# H01R0_Backend.net
KiCad netlist of a schematic drawn in Altium Designer
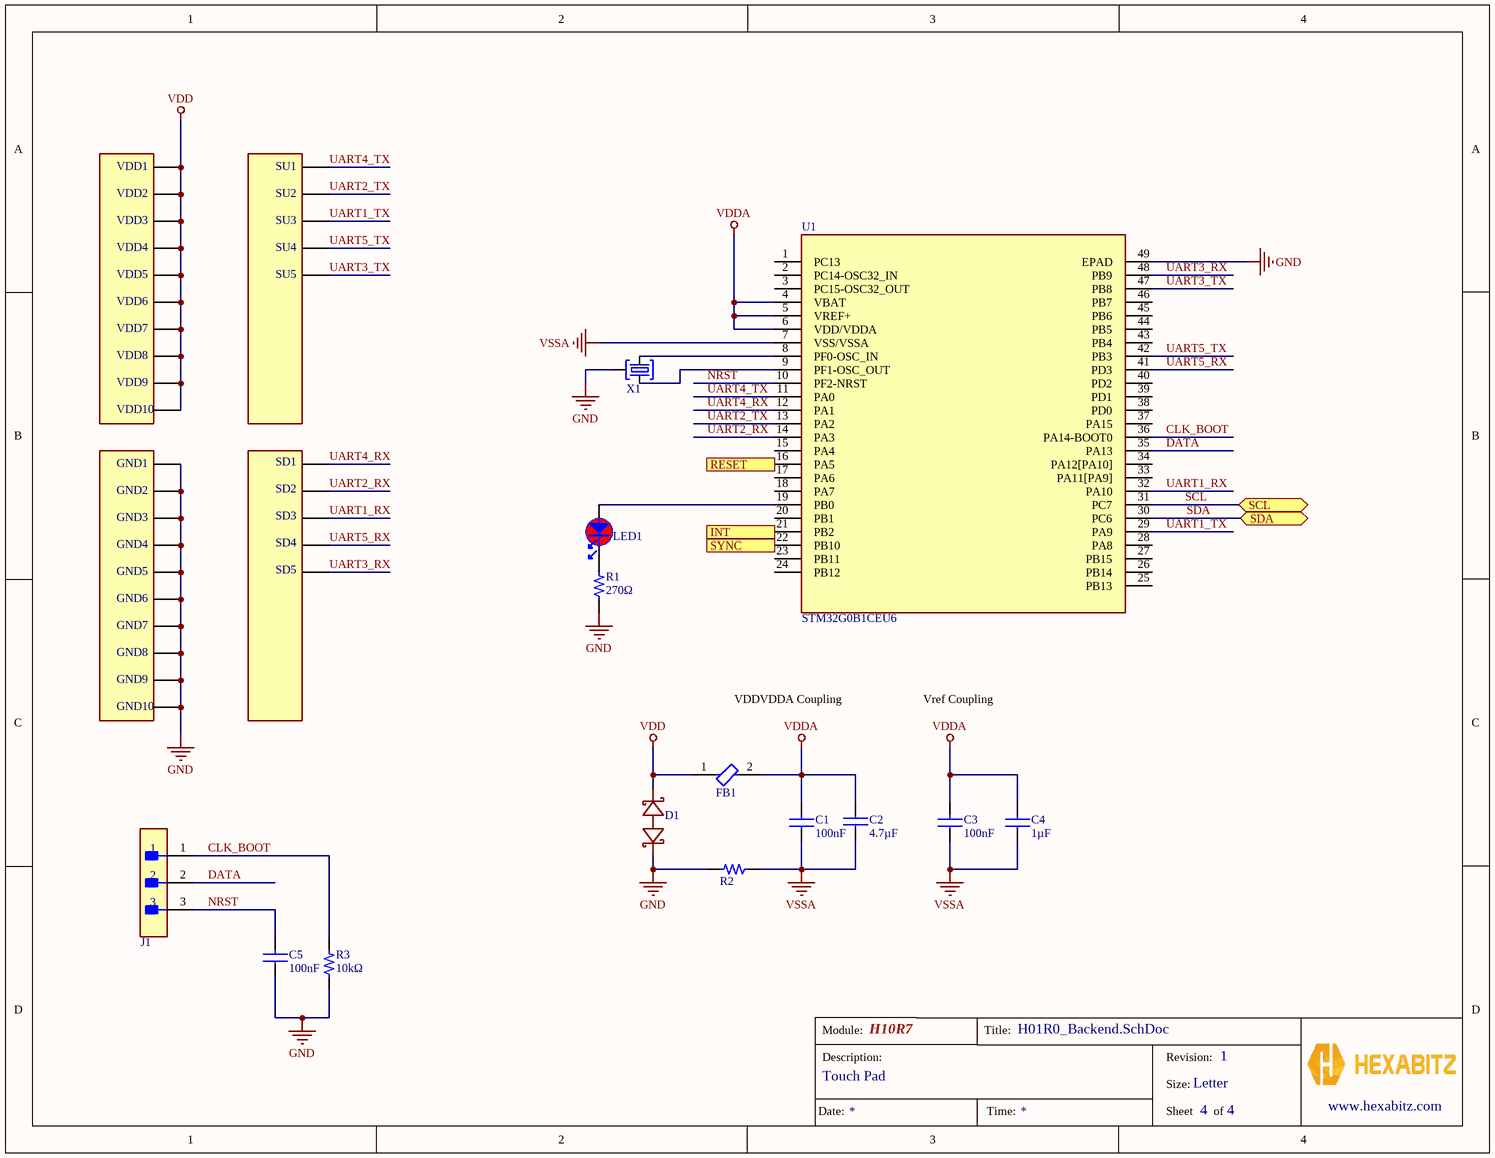
[diagram p0: H01R0_Backend.SchDoc]

(export (version "E")
  (design (tool "Eeschema 10.0.6"))
  (components
    (comp (ref "C1")
      (value "100nF")
      (footprint "C0603")
      (fields
        (field (name "MANUFACTURER") "Samsung Electro-Mechanics")
        (field (name "MANUFACTURER PART NUMBER") "CL10B104KA8NNNC")
        (field (name "TOLERANCE") "10%")
      )
      (libsource (lib "Hexabitz Altium Library") (part "generic Capacitor"))
    )
    (comp (ref "C2")
      (value "4.7µF")
      (footprint "C0805")
      (fields
        (field (name "MANUFACTURER") "Samsung Electro-Mechanics")
        (field (name "MANUFACTURER PART NUMBER") "CL21X475KAQNNNE")
        (field (name "TOLERANCE") "10%")
      )
      (libsource (lib "Hexabitz Altium Library") (part "generic Capacitor"))
    )
    (comp (ref "C3")
      (value "100nF")
      (footprint "C0603")
      (fields
        (field (name "MANUFACTURER") "Samsung Electro-Mechanics")
        (field (name "MANUFACTURER PART NUMBER") "CL10B104KA8NNNC")
        (field (name "TOLERANCE") "10%")
      )
      (libsource (lib "Hexabitz Altium Library") (part "generic Capacitor"))
    )
    (comp (ref "C4")
      (value "1µF")
      (footprint "C0805")
      (description "Ceramic Capacitor, Ceramic, 16V, 10% +Tol, 10% -Tol, X7R, 15% TC, 1uF, Surface Mount, 0805")
      (fields
        (field (name "MANUFACTURER") "Yageo Group")
        (field (name "MANUFACTURER PART NUMBER") "CC0805KKX7R7BB105")
      )
      (libsource (lib "Hexabitz Altium Library") (part "generic Capacitor"))
    )
    (comp (ref "C5")
      (value "100nF")
      (footprint "C0603")
      (fields
        (field (name "MANUFACTURER") "Samsung Electro-Mechanics")
        (field (name "MANUFACTURER PART NUMBER") "CL10B104KA8NNNC")
        (field (name "TOLERANCE") "10%")
      )
      (libsource (lib "Hexabitz Altium Library") (part "generic Capacitor"))
    )
    (comp (ref "D1")
      (value "CDSOD323-T03SC")
      (footprint "SOD2513X114N")
      (description "A 3V, 350W, bi-directional, standard capacitance, SOD323 pkg TVS Diode ¦ Bourns CDSOD323-T03SC")
      (fields (field (name "MANUFACTURER") "Bourns"))
      (libsource (lib "Hexabitz Altium Library") (part "CDSOD323-T03SC"))
    )
    (comp (ref "FB1")
      (value "MMZ1608Y300B")
      (footprint "FP-MMZ1608-0_8-MFG")
      (description "Ferrite Beads 0603 30ohms 1500mA Signal Line AEC-Q200")
      (fields
        (field (name "MANUFACTURER") "TDK")
        (field (name "MANUFACTURER PART NUMBER") "MMZ1608Y300BTD25")
      )
      (libsource (lib "Hexabitz Altium Library") (part "MMZ1608Y300B"))
    )
    (comp (ref "GND1")
      (value "HEXABIT_UART_PORT")
      (footprint "HEXABIT_POWER_PORT_D")
      (libsource (lib "hexabitz_connectors.Library") (part "HEXABIT_POWER_PORT_D"))
    )
    (comp (ref "GND2")
      (value "HEXABIT_UART_PORT")
      (footprint "HEXABIT_POWER_PORT_D")
      (libsource (lib "hexabitz_connectors.Library") (part "HEXABIT_POWER_PORT_D"))
    )
    (comp (ref "GND3")
      (value "HEXABIT_UART_PORT")
      (footprint "HEXABIT_POWER_PORT_D_300R")
      (libsource (lib "hexabitz_connectors.Library") (part "HEXABIT_POWER_PORT_D_300R"))
    )
    (comp (ref "GND4")
      (value "HEXABIT_UART_PORT")
      (footprint "HEXABIT_POWER_PORT_D")
      (libsource (lib "hexabitz_connectors.Library") (part "HEXABIT_POWER_PORT_D"))
    )
    (comp (ref "GND5")
      (value "HEXABIT_UART_PORT")
      (footprint "HEXABIT_POWER_PORT_D")
      (libsource (lib "hexabitz_connectors.Library") (part "HEXABIT_POWER_PORT_D"))
    )
    (comp (ref "GND6")
      (value "HEXABIT_UART_PORT")
      (footprint "HEXABIT_POWER_PORT_D")
      (libsource (lib "hexabitz_connectors.Library") (part "HEXABIT_POWER_PORT_D"))
    )
    (comp (ref "GND7")
      (value "HEXABIT_UART_PORT")
      (footprint "HEXABIT_POWER_PORT_D")
      (libsource (lib "hexabitz_connectors.Library") (part "HEXABIT_POWER_PORT_D"))
    )
    (comp (ref "GND8")
      (value "HEXABIT_UART_PORT")
      (footprint "HEXABIT_POWER_PORT_D_300L")
      (libsource (lib "hexabitz_connectors.Library") (part "HEXABIT_POWER_PORT_D_300L"))
    )
    (comp (ref "GND9")
      (value "HEXABIT_UART_PORT")
      (footprint "HEXABIT_POWER_PORT_D")
      (libsource (lib "hexabitz_connectors.Library") (part "HEXABIT_POWER_PORT_D"))
    )
    (comp (ref "GND10")
      (value "HEXABIT_UART_PORT")
      (footprint "HEXABIT_POWER_PORT_D")
      (libsource (lib "hexabitz_connectors.Library") (part "HEXABIT_POWER_PORT_D"))
    )
    (comp (ref "J1")
      (value "TSW-103-14-G-S")
      (footprint "FP-TSW-103-14-G-S-MFG")
      (description "CONN HEADER VERT 3POS 2.54MM")
      (libsource (lib "Altium Content Vault") (part "cd3439d6ef35ae5d9b27ec4fdd3e828"))
    )
    (comp (ref "LED1")
      (value "VLMS1300-GS08")
      (footprint "FP-6_541-5092_01-4-MFG")
      (description "LED Uni-Color Super Red 639nm 2-Pin Chip 0603(1608Metric) T/R")
      (fields (field (name "MANUFACTURER") "Vishay Semiconductors"))
      (libsource (lib "Hexabitz Altium Library") (part "VLMS1300-GS08"))
    )
    (comp (ref "R1")
      (value "270Ω")
      (footprint "R0603")
      (description "Res Thick Film 0603 270 Ohm 5% 0.1W(1/10W) ±200ppm/C Pad SMD Automotive T/R")
      (fields
        (field (name "MANUFACTURER") "Panasonic")
        (field (name "MANUFACTURER PART NUMBER") "ERJ-3GEYJ271V")
      )
      (libsource (lib "") (part "generic Resistor_1"))
    )
    (comp (ref "R2")
      (value "Manufacturer Part Number")
      (footprint "R0603")
      (libsource (lib "Hexabitz Altium Library") (part "generic Resistor"))
    )
    (comp (ref "R3")
      (value "10kΩ")
      (footprint "R0603")
      (description "100mW Thick Film Resistors ±100ppm/℃ ±1% 10kΩ 0603 Chip Resistor - Surface Mount ROHS")
      (fields
        (field (name "MANUFACTURER") "Yageo Group")
        (field (name "MANUFACTURER PART NUMBER") "RC0603FR-0710KL")
      )
      (libsource (lib "") (part "generic Resistor_2"))
    )
    (comp (ref "SD1")
      (value "HEXABIT_UART_PORT")
      (footprint "HEXABIT_UART_PORT_D")
      (libsource (lib "hexabitz_connectors.Library") (part "HEXABIT_UART_PORT_D"))
    )
    (comp (ref "SD2")
      (value "HEXABIT_UART_PORT")
      (footprint "HEXABIT_UART_PORT_D")
      (libsource (lib "hexabitz_connectors.Library") (part "HEXABIT_UART_PORT_D"))
    )
    (comp (ref "SD3")
      (value "HEXABIT_UART_PORT")
      (footprint "HEXABIT_UART_PORT_D")
      (libsource (lib "hexabitz_connectors.Library") (part "HEXABIT_UART_PORT_D"))
    )
    (comp (ref "SD4")
      (value "HEXABIT_UART_PORT")
      (footprint "HEXABIT_UART_PORT_D")
      (libsource (lib "hexabitz_connectors.Library") (part "HEXABIT_UART_PORT_D"))
    )
    (comp (ref "SD5")
      (value "HEXABIT_UART_PORT")
      (footprint "HEXABIT_UART_PORT_D")
      (libsource (lib "hexabitz_connectors.Library") (part "HEXABIT_UART_PORT_D"))
    )
    (comp (ref "SU1")
      (value "HEXABIT_UART_PORT")
      (footprint "HEXABIT_UART_PORT_U")
      (libsource (lib "hexabitz_connectors.Library") (part "HEXABIT_UART_PORT_U"))
    )
    (comp (ref "SU2")
      (value "HEXABIT_UART_PORT")
      (footprint "HEXABIT_UART_PORT_U")
      (libsource (lib "hexabitz_connectors.Library") (part "HEXABIT_UART_PORT_U"))
    )
    (comp (ref "SU3")
      (value "HEXABIT_UART_PORT")
      (footprint "HEXABIT_UART_PORT_U")
      (libsource (lib "hexabitz_connectors.Library") (part "HEXABIT_UART_PORT_U"))
    )
    (comp (ref "SU4")
      (value "HEXABIT_UART_PORT")
      (footprint "HEXABIT_UART_PORT_U")
      (libsource (lib "hexabitz_connectors.Library") (part "HEXABIT_UART_PORT_U"))
    )
    (comp (ref "SU5")
      (value "HEXABIT_UART_PORT")
      (footprint "HEXABIT_UART_PORT_U")
      (libsource (lib "hexabitz_connectors.Library") (part "HEXABIT_UART_PORT_U"))
    )
    (comp (ref "U1")
      (value "STM32G0B1CEU6")
      (footprint "QFN50P700X700X65-49N-D")
      (description "MCU 32-bit ARM Cortex M0+ RISC 512KB Flash 1.8V/2.5V/3.3V 48-Pin UFQFPN EP Tray")
      (fields
        (field (name "MANUFACTURER") "STMicroelectronics")
        (field (name "MANUFACTURER PART NUMBER") "STM32G0B1CEU6")
      )
      (libsource (lib "Hexabitz Altium Library") (part "STM32G0B1CEU6"))
    )
    (comp (ref "VDD1")
      (value "HEXABIT_UART_PORT")
      (footprint "HEXABIT_POWER_PORT_U")
      (libsource (lib "hexabitz_connectors.Library") (part "HEXABIT_POWER_PORT_U"))
    )
    (comp (ref "VDD2")
      (value "HEXABIT_UART_PORT")
      (footprint "HEXABIT_POWER_PORT_U")
      (libsource (lib "hexabitz_connectors.Library") (part "HEXABIT_POWER_PORT_U"))
    )
    (comp (ref "VDD3")
      (value "HEXABIT_UART_PORT")
      (footprint "HEXABIT_POWER_PORT_U_300R")
      (libsource (lib "hexabitz_connectors.Library") (part "HEXABIT_POWER_PORT_U_300R"))
    )
    (comp (ref "VDD4")
      (value "HEXABIT_UART_PORT")
      (footprint "HEXABIT_POWER_PORT_U")
      (libsource (lib "hexabitz_connectors.Library") (part "HEXABIT_POWER_PORT_U"))
    )
    (comp (ref "VDD5")
      (value "HEXABIT_UART_PORT")
      (footprint "HEXABIT_POWER_PORT_U")
      (libsource (lib "hexabitz_connectors.Library") (part "HEXABIT_POWER_PORT_U"))
    )
    (comp (ref "VDD6")
      (value "HEXABIT_UART_PORT")
      (footprint "HEXABIT_POWER_PORT_U")
      (libsource (lib "hexabitz_connectors.Library") (part "HEXABIT_POWER_PORT_U"))
    )
    (comp (ref "VDD7")
      (value "HEXABIT_UART_PORT")
      (footprint "HEXABIT_POWER_PORT_U")
      (libsource (lib "hexabitz_connectors.Library") (part "HEXABIT_POWER_PORT_U"))
    )
    (comp (ref "VDD8")
      (value "HEXABIT_UART_PORT")
      (footprint "HEXABIT_POWER_PORT_U_300L")
      (libsource (lib "hexabitz_connectors.Library") (part "HEXABIT_POWER_PORT_U_300L"))
    )
    (comp (ref "VDD9")
      (value "HEXABIT_UART_PORT")
      (footprint "HEXABIT_POWER_PORT_U")
      (libsource (lib "hexabitz_connectors.Library") (part "HEXABIT_POWER_PORT_U"))
    )
    (comp (ref "VDD10")
      (value "HEXABIT_UART_PORT")
      (footprint "HEXABIT_POWER_PORT_U")
      (libsource (lib "hexabitz_connectors.Library") (part "HEXABIT_POWER_PORT_U"))
    )
    (comp (ref "X1")
      (value "CSTCE8M00G52Z-R0")
      (footprint "XTALL_CSTCE8M00G52")
      (description "Ceramic Resonator 8MHz ±0.5% (Tol) ±0.2% (Stability) 10pF 40Ohm 3-Pin CSMD T/R")
      (fields (field (name "MANUFACTURER") "Murata") (field (name "TOLERANCE") "0.5%"))
      (libsource (lib "Hexabitz Altium Library") (part "CSTCE8M00G52Z-R0"))
    )
  )
  (nets
    (net (code "1") (name "/CLK_BOOT") (class "Default")
      (node (ref "J1") (pin "1") (pinfunction "1_1") (pintype "passive"))
      (node (ref "R3") (pin "1") (pinfunction "1_1") (pintype "passive"))
      (node (ref "U1") (pin "36") (pinfunction "PA14-BOOT0_36") (pintype "passive"))
    )
    (net (code "2") (name "/DATA") (class "Default")
      (node (ref "J1") (pin "2") (pinfunction "2_2") (pintype "passive"))
      (node (ref "U1") (pin "35") (pinfunction "PA13_35") (pintype "passive"))
    )
    (net (code "3") (name "/INT") (class "Default")
      (node (ref "U1") (pin "21") (pinfunction "PB2_21") (pintype "passive"))
    )
    (net (code "4") (name "/NRST") (class "Default")
      (node (ref "C5") (pin "2") (pinfunction "2_2") (pintype "passive"))
      (node (ref "J1") (pin "3") (pinfunction "3_3") (pintype "passive"))
      (node (ref "U1") (pin "10") (pinfunction "PF2-NRST_10") (pintype "passive"))
    )
    (net (code "5") (name "/RESET") (class "Default")
      (node (ref "U1") (pin "16") (pinfunction "PA5_16") (pintype "passive"))
    )
    (net (code "6") (name "/SCL") (class "Default")
      (node (ref "U1") (pin "31") (pinfunction "PC7_31") (pintype "passive"))
    )
    (net (code "7") (name "/SDA") (class "Default")
      (node (ref "U1") (pin "30") (pinfunction "PC6_30") (pintype "passive"))
    )
    (net (code "8") (name "/SYNC") (class "Default")
      (node (ref "U1") (pin "22") (pinfunction "PB10_22") (pintype "passive"))
    )
    (net (code "9") (name "/UART1_RX") (class "Default")
      (node (ref "SD3") (pin "UART_D") (pinfunction "UART_D_UART_D") (pintype "passive"))
      (node (ref "U1") (pin "32") (pinfunction "PA10_32") (pintype "passive"))
    )
    (net (code "10") (name "/UART1_TX") (class "Default")
      (node (ref "SU3") (pin "UART_U") (pinfunction "UART_U_UART_U") (pintype "passive"))
      (node (ref "U1") (pin "29") (pinfunction "PA9_29") (pintype "passive"))
    )
    (net (code "11") (name "/UART2_RX") (class "Default")
      (node (ref "SD2") (pin "UART_D") (pinfunction "UART_D_UART_D") (pintype "passive"))
      (node (ref "U1") (pin "14") (pinfunction "PA3_14") (pintype "passive"))
    )
    (net (code "12") (name "/UART2_TX") (class "Default")
      (node (ref "SU2") (pin "UART_U") (pinfunction "UART_U_UART_U") (pintype "passive"))
      (node (ref "U1") (pin "13") (pinfunction "PA2_13") (pintype "passive"))
    )
    (net (code "13") (name "/UART3_RX") (class "Default")
      (node (ref "SD5") (pin "UART_D") (pinfunction "UART_D_UART_D") (pintype "passive"))
      (node (ref "U1") (pin "48") (pinfunction "PB9_48") (pintype "passive"))
    )
    (net (code "14") (name "/UART3_TX") (class "Default")
      (node (ref "SU5") (pin "UART_U") (pinfunction "UART_U_UART_U") (pintype "passive"))
      (node (ref "U1") (pin "47") (pinfunction "PB8_47") (pintype "passive"))
    )
    (net (code "15") (name "/UART4_RX") (class "Default")
      (node (ref "SD1") (pin "UART_D") (pinfunction "UART_D_UART_D") (pintype "passive"))
      (node (ref "U1") (pin "12") (pinfunction "PA1_12") (pintype "passive"))
    )
    (net (code "16") (name "/UART4_TX") (class "Default")
      (node (ref "SU1") (pin "UART_U") (pinfunction "UART_U_UART_U") (pintype "passive"))
      (node (ref "U1") (pin "11") (pinfunction "PA0_11") (pintype "passive"))
    )
    (net (code "17") (name "/UART5_RX") (class "Default")
      (node (ref "SD4") (pin "UART_D") (pinfunction "UART_D_UART_D") (pintype "passive"))
      (node (ref "U1") (pin "41") (pinfunction "PD3_41") (pintype "passive"))
    )
    (net (code "18") (name "/UART5_TX") (class "Default")
      (node (ref "SU4") (pin "UART_U") (pinfunction "UART_U_UART_U") (pintype "passive"))
      (node (ref "U1") (pin "42") (pinfunction "PB3_42") (pintype "passive"))
    )
    (net (code "19") (name "GND") (class "Default")
      (node (ref "C5") (pin "1") (pinfunction "1_1") (pintype "passive"))
      (node (ref "D1") (pin "1") (pinfunction "A_1") (pintype "passive"))
      (node (ref "GND1") (pin "Pwr_D") (pinfunction "Pwr_D_Pwr_D") (pintype "passive"))
      (node (ref "GND10") (pin "Pwr_D") (pinfunction "Pwr_D_Pwr_D") (pintype "passive"))
      (node (ref "GND2") (pin "Pwr_D") (pinfunction "Pwr_D_Pwr_D") (pintype "passive"))
      (node (ref "GND3") (pin "Pwr_D") (pinfunction "Pwr_D_Pwr_D") (pintype "passive"))
      (node (ref "GND4") (pin "Pwr_D") (pinfunction "Pwr_D_Pwr_D") (pintype "passive"))
      (node (ref "GND5") (pin "Pwr_D") (pinfunction "Pwr_D_Pwr_D") (pintype "passive"))
      (node (ref "GND6") (pin "Pwr_D") (pinfunction "Pwr_D_Pwr_D") (pintype "passive"))
      (node (ref "GND7") (pin "Pwr_D") (pinfunction "Pwr_D_Pwr_D") (pintype "passive"))
      (node (ref "GND8") (pin "Pwr_D") (pinfunction "Pwr_D_Pwr_D") (pintype "passive"))
      (node (ref "GND9") (pin "Pwr_D") (pinfunction "Pwr_D_Pwr_D") (pintype "passive"))
      (node (ref "R1") (pin "1") (pinfunction "1_1") (pintype "passive"))
      (node (ref "R2") (pin "1") (pinfunction "1_1") (pintype "passive"))
      (node (ref "R3") (pin "2") (pinfunction "2_2") (pintype "passive"))
      (node (ref "U1") (pin "49") (pinfunction "EPAD_49") (pintype "passive"))
      (node (ref "X1") (pin "P$2") (pinfunction "2_P$2") (pintype "passive"))
    )
    (net (code "20") (name "Net-(LED1-Pad1)") (class "Default")
      (node (ref "LED1") (pin "1") (pintype "passive"))
      (node (ref "R1") (pin "2") (pinfunction "2_2") (pintype "passive"))
    )
    (net (code "21") (name "Net-(U1-PB0)") (class "Default")
      (node (ref "LED1") (pin "2") (pintype "passive"))
      (node (ref "U1") (pin "19") (pinfunction "PB0_19") (pintype "passive"))
    )
    (net (code "22") (name "Net-(U1-PF0-OSC_IN)") (class "Default")
      (node (ref "U1") (pin "8") (pinfunction "PF0-OSC_IN_8") (pintype "passive"))
      (node (ref "X1") (pin "P$3") (pinfunction "3_P$3") (pintype "passive"))
    )
    (net (code "23") (name "Net-(U1-PF1-OSC_OUT)") (class "Default")
      (node (ref "U1") (pin "9") (pinfunction "PF1-OSC_OUT_9") (pintype "passive"))
      (node (ref "X1") (pin "P$1") (pinfunction "1_P$1") (pintype "passive"))
    )
    (net (code "24") (name "VDD") (class "Default")
      (node (ref "D1") (pin "2") (pinfunction "C_2") (pintype "passive"))
      (node (ref "FB1") (pin "1") (pinfunction "1_1") (pintype "passive"))
      (node (ref "VDD1") (pin "Pwr_U") (pinfunction "Pwr_U_Pwr_U") (pintype "passive"))
      (node (ref "VDD10") (pin "Pwr_U") (pinfunction "Pwr_U_Pwr_U") (pintype "passive"))
      (node (ref "VDD2") (pin "Pwr_U") (pinfunction "Pwr_U_Pwr_U") (pintype "passive"))
      (node (ref "VDD3") (pin "Pwr_U") (pinfunction "Pwr_U_Pwr_U") (pintype "passive"))
      (node (ref "VDD4") (pin "Pwr_U") (pinfunction "Pwr_U_Pwr_U") (pintype "passive"))
      (node (ref "VDD5") (pin "Pwr_U") (pinfunction "Pwr_U_Pwr_U") (pintype "passive"))
      (node (ref "VDD6") (pin "Pwr_U") (pinfunction "Pwr_U_Pwr_U") (pintype "passive"))
      (node (ref "VDD7") (pin "Pwr_U") (pinfunction "Pwr_U_Pwr_U") (pintype "passive"))
      (node (ref "VDD8") (pin "Pwr_U") (pinfunction "Pwr_U_Pwr_U") (pintype "passive"))
      (node (ref "VDD9") (pin "Pwr_U") (pinfunction "Pwr_U_Pwr_U") (pintype "passive"))
    )
    (net (code "25") (name "VDDA") (class "Default")
      (node (ref "C1") (pin "2") (pinfunction "2_2") (pintype "passive"))
      (node (ref "C2") (pin "1") (pinfunction "1_1") (pintype "passive"))
      (node (ref "C3") (pin "2") (pinfunction "2_2") (pintype "passive"))
      (node (ref "C4") (pin "2") (pinfunction "2_2") (pintype "passive"))
      (node (ref "FB1") (pin "2") (pinfunction "2_2") (pintype "passive"))
      (node (ref "U1") (pin "4") (pinfunction "VBAT_4") (pintype "passive"))
      (node (ref "U1") (pin "5") (pinfunction "VREF+_5") (pintype "passive"))
      (node (ref "U1") (pin "6") (pinfunction "VDD/VDDA_6") (pintype "passive"))
    )
    (net (code "26") (name "VSSA") (class "Default")
      (node (ref "C1") (pin "1") (pinfunction "1_1") (pintype "passive"))
      (node (ref "C2") (pin "2") (pinfunction "2_2") (pintype "passive"))
      (node (ref "C3") (pin "1") (pinfunction "1_1") (pintype "passive"))
      (node (ref "C4") (pin "1") (pinfunction "1_1") (pintype "passive"))
      (node (ref "R2") (pin "2") (pinfunction "2_2") (pintype "passive"))
      (node (ref "U1") (pin "7") (pinfunction "VSS/VSSA_7") (pintype "passive"))
    )
    (net (code "27") (name "unconnected-(U1-PA4-Pad15)") (class "Default")
      (node (ref "U1") (pin "15") (pinfunction "PA4_15") (pintype "passive"))
    )
    (net (code "28") (name "unconnected-(U1-PA6-Pad17)") (class "Default")
      (node (ref "U1") (pin "17") (pinfunction "PA6_17") (pintype "passive"))
    )
    (net (code "29") (name "unconnected-(U1-PA7-Pad18)") (class "Default")
      (node (ref "U1") (pin "18") (pinfunction "PA7_18") (pintype "passive"))
    )
    (net (code "30") (name "unconnected-(U1-PA8-Pad28)") (class "Default")
      (node (ref "U1") (pin "28") (pinfunction "PA8_28") (pintype "passive"))
    )
    (net (code "31") (name "unconnected-(U1-PA11[PA9]-Pad33)") (class "Default")
      (node (ref "U1") (pin "33") (pinfunction "PA11[PA9]_33") (pintype "passive"))
    )
    (net (code "32") (name "unconnected-(U1-PA12[PA10]-Pad34)") (class "Default")
      (node (ref "U1") (pin "34") (pinfunction "PA12[PA10]_34") (pintype "passive"))
    )
    (net (code "33") (name "unconnected-(U1-PA15-Pad37)") (class "Default")
      (node (ref "U1") (pin "37") (pinfunction "PA15_37") (pintype "passive"))
    )
    (net (code "34") (name "unconnected-(U1-PB1-Pad20)") (class "Default")
      (node (ref "U1") (pin "20") (pinfunction "PB1_20") (pintype "passive"))
    )
    (net (code "35") (name "unconnected-(U1-PB4-Pad43)") (class "Default")
      (node (ref "U1") (pin "43") (pinfunction "PB4_43") (pintype "passive"))
    )
    (net (code "36") (name "unconnected-(U1-PB5-Pad44)") (class "Default")
      (node (ref "U1") (pin "44") (pinfunction "PB5_44") (pintype "passive"))
    )
    (net (code "37") (name "unconnected-(U1-PB6-Pad45)") (class "Default")
      (node (ref "U1") (pin "45") (pinfunction "PB6_45") (pintype "passive"))
    )
    (net (code "38") (name "unconnected-(U1-PB7-Pad46)") (class "Default")
      (node (ref "U1") (pin "46") (pinfunction "PB7_46") (pintype "passive"))
    )
    (net (code "39") (name "unconnected-(U1-PB11-Pad23)") (class "Default")
      (node (ref "U1") (pin "23") (pinfunction "PB11_23") (pintype "passive"))
    )
    (net (code "40") (name "unconnected-(U1-PB12-Pad24)") (class "Default")
      (node (ref "U1") (pin "24") (pinfunction "PB12_24") (pintype "passive"))
    )
    (net (code "41") (name "unconnected-(U1-PB13-Pad25)") (class "Default")
      (node (ref "U1") (pin "25") (pinfunction "PB13_25") (pintype "passive"))
    )
    (net (code "42") (name "unconnected-(U1-PB14-Pad26)") (class "Default")
      (node (ref "U1") (pin "26") (pinfunction "PB14_26") (pintype "passive"))
    )
    (net (code "43") (name "unconnected-(U1-PB15-Pad27)") (class "Default")
      (node (ref "U1") (pin "27") (pinfunction "PB15_27") (pintype "passive"))
    )
    (net (code "44") (name "unconnected-(U1-PC13-Pad1)") (class "Default")
      (node (ref "U1") (pin "1") (pinfunction "PC13_1") (pintype "passive"))
    )
    (net (code "45") (name "unconnected-(U1-PC14-OSC32_IN-Pad2)") (class "Default")
      (node (ref "U1") (pin "2") (pinfunction "PC14-OSC32_IN_2") (pintype "passive"))
    )
    (net (code "46") (name "unconnected-(U1-PC15-OSC32_OUT-Pad3)") (class "Default")
      (node (ref "U1") (pin "3") (pinfunction "PC15-OSC32_OUT_3") (pintype "passive"))
    )
    (net (code "47") (name "unconnected-(U1-PD0-Pad38)") (class "Default")
      (node (ref "U1") (pin "38") (pinfunction "PD0_38") (pintype "passive"))
    )
    (net (code "48") (name "unconnected-(U1-PD1-Pad39)") (class "Default")
      (node (ref "U1") (pin "39") (pinfunction "PD1_39") (pintype "passive"))
    )
    (net (code "49") (name "unconnected-(U1-PD2-Pad40)") (class "Default")
      (node (ref "U1") (pin "40") (pinfunction "PD2_40") (pintype "passive"))
    )
  )
)
